# CHANNEL_DELAY.net
KiCad netlist of a schematic drawn in Altium Designer
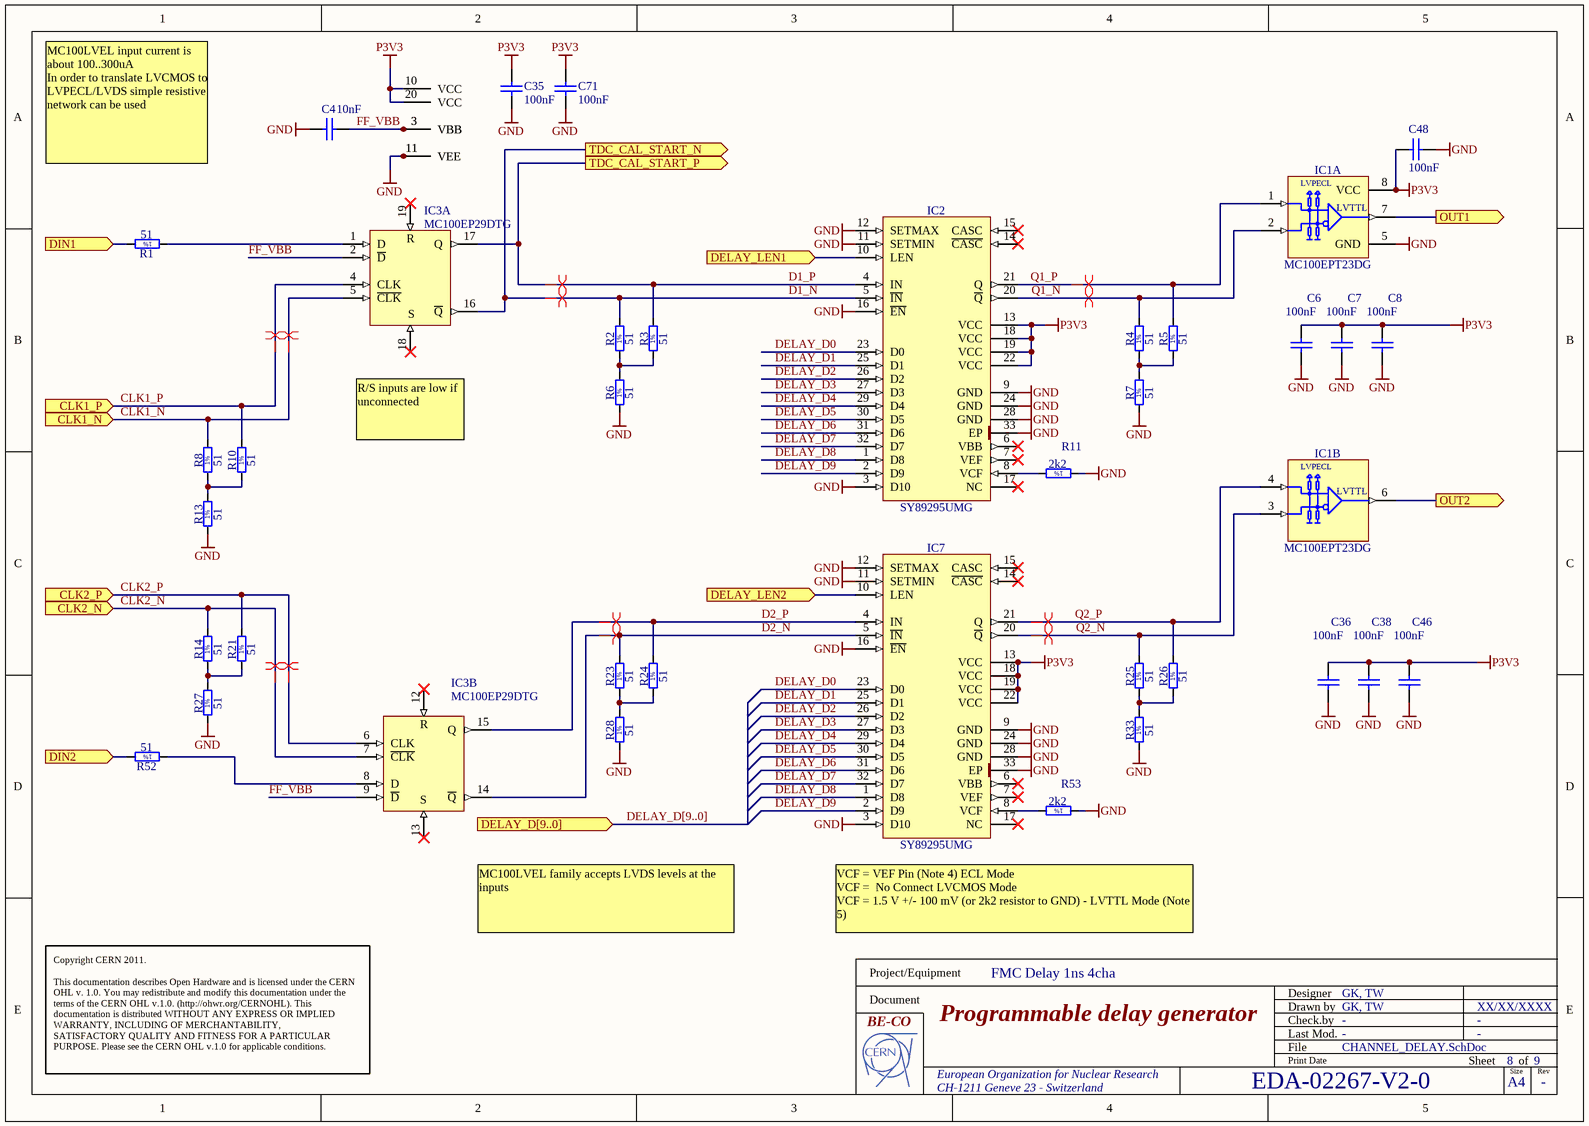
[diagram p0: CHANNEL_DELAY.SchDoc]

(export (version "E")
  (design (tool "Eeschema 10.0.6"))
  (components
    (comp (ref "C4")
      (value "10nF")
      (footprint "CAPC1608X87N")
      (description "Non-polarised capacitor")
      (fields
        (field (name "PART NUMBER") "CC0603_10NF_50V_10%_X7R")
        (field (name "VOLTAGE") "50V")
        (field (name "AUTHOR") "CERN DEM JLC")
      )
      (libsource (lib "Capacitors") (part "Capacitor - non polarized"))
    )
    (comp (ref "C6")
      (value "100nF")
      (footprint "CAPC1608X87N")
      (description "Non-polarised capacitor")
      (fields
        (field (name "MANUFACTURER1 PART NUMBER") "223858615649")
        (field (name "MANUFACTURER") "GENERIC")
        (field (name "AUTHOR") "CERN DEM JLC")
      )
      (libsource (lib "Capacitors") (part "Capacitor - non polarized"))
    )
    (comp (ref "C7")
      (value "100nF")
      (footprint "CAPC1608X87N")
      (description "Non-polarised capacitor")
      (fields
        (field (name "MANUFACTURER1 PART NUMBER") "223858615649")
        (field (name "MANUFACTURER") "GENERIC")
        (field (name "AUTHOR") "CERN DEM JLC")
      )
      (libsource (lib "Capacitors") (part "Capacitor - non polarized"))
    )
    (comp (ref "C8")
      (value "100nF")
      (footprint "CAPC1608X87N")
      (description "Non-polarised capacitor")
      (fields
        (field (name "MANUFACTURER1 PART NUMBER") "223858615649")
        (field (name "MANUFACTURER") "GENERIC")
        (field (name "AUTHOR") "CERN DEM JLC")
      )
      (libsource (lib "Capacitors") (part "Capacitor - non polarized"))
    )
    (comp (ref "C35")
      (value "100nF")
      (footprint "CAPC1608X87N")
      (description "Non-polarised capacitor")
      (fields
        (field (name "MANUFACTURER1 PART NUMBER") "223858615649")
        (field (name "MANUFACTURER") "GENERIC")
        (field (name "AUTHOR") "CERN DEM JLC")
      )
      (libsource (lib "Capacitors") (part "Capacitor - non polarized"))
    )
    (comp (ref "C36")
      (value "100nF")
      (footprint "CAPC1608X87N")
      (description "Non-polarised capacitor")
      (fields
        (field (name "MANUFACTURER1 PART NUMBER") "223858615649")
        (field (name "MANUFACTURER") "GENERIC")
        (field (name "AUTHOR") "CERN DEM JLC")
      )
      (libsource (lib "Capacitors") (part "Capacitor - non polarized"))
    )
    (comp (ref "C38")
      (value "100nF")
      (footprint "CAPC1608X87N")
      (description "Non-polarised capacitor")
      (fields
        (field (name "MANUFACTURER1 PART NUMBER") "223858615649")
        (field (name "MANUFACTURER") "GENERIC")
        (field (name "AUTHOR") "CERN DEM JLC")
      )
      (libsource (lib "Capacitors") (part "Capacitor - non polarized"))
    )
    (comp (ref "C46")
      (value "100nF")
      (footprint "CAPC1608X87N")
      (description "Non-polarised capacitor")
      (fields
        (field (name "MANUFACTURER1 PART NUMBER") "223858615649")
        (field (name "MANUFACTURER") "GENERIC")
        (field (name "AUTHOR") "CERN DEM JLC")
      )
      (libsource (lib "Capacitors") (part "Capacitor - non polarized"))
    )
    (comp (ref "C48")
      (value "100nF")
      (footprint "CAPC1608X87N")
      (description "Non-polarised capacitor")
      (fields
        (field (name "MANUFACTURER1 PART NUMBER") "223858615649")
        (field (name "MANUFACTURER") "GENERIC")
        (field (name "AUTHOR") "CERN DEM JLC")
      )
      (libsource (lib "Capacitors") (part "Capacitor - non polarized"))
    )
    (comp (ref "C71")
      (value "100nF")
      (footprint "CAPC1608X87N")
      (description "Non-polarised capacitor")
      (fields
        (field (name "MANUFACTURER1 PART NUMBER") "223858615649")
        (field (name "MANUFACTURER") "GENERIC")
        (field (name "AUTHOR") "CERN DEM JLC")
      )
      (libsource (lib "Capacitors") (part "Capacitor - non polarized"))
    )
    (comp (ref "IC1")
      (value "MC100EPT23DG")
      (footprint "SOIC127P600X175-8N")
      (description "3.3V Dual Differential LVPECL/LVDS/CML  to LVTTL/LVCMOS Translator")
      (fields (field (name "MANUFACTURER") "ON SEMICONDUCTOR") (field (name "AUTHOR") "CERN DEM JLC"))
      (libsource (lib "ICs And Semiconductors") (part "100EPT23D"))
    )
    (comp (ref "IC2")
      (value "SY89295UMG")
      (footprint "QFN50P500X500X90-33N-S320")
      (description "2.5V/3.3V 1.5GHz Precision LVPECL Programmable Delay")
      (fields (field (name "MANUFACTURER") "MICREL") (field (name "AUTHOR") "CERN DEM JLC"))
      (libsource (lib "ICs And Semiconductors") (part "SY89295UMG"))
    )
    (comp (ref "IC3")
      (value "MC100EP29DTG")
      (footprint "SOP65P640X120-20N")
      (description "3.3V/5V ECL Dual Differential Data and Clock D Flip-Flop With Set and Reset")
      (fields (field (name "MANUFACTURER") "ON SEMICONDUCTOR") (field (name "AUTHOR") "CERN DEM JLC"))
      (libsource (lib "ICs And Semiconductors") (part "100EP29D"))
    )
    (comp (ref "IC7")
      (value "SY89295UMG")
      (footprint "QFN50P500X500X90-33N-S320")
      (description "2.5V/3.3V 1.5GHz Precision LVPECL Programmable Delay")
      (fields (field (name "MANUFACTURER") "MICREL") (field (name "AUTHOR") "CERN DEM JLC"))
      (libsource (lib "ICs And Semiconductors") (part "SY89295UMG"))
    )
    (comp (ref "R1")
      (value "51")
      (footprint "RESC1608X55N")
      (description "Resistor - 1%")
      (fields
        (field (name "PART NUMBER") "R0603_51R_1%_0.1W_100PPM")
        (field (name "POWER") "0.1W")
        (field (name "AUTHOR") "CERN DEM JLC")
      )
      (libsource (lib "Resistors") (part "Resistor - 1%"))
    )
    (comp (ref "R2")
      (value "51")
      (footprint "RESC1608X55N")
      (description "Resistor - 1%")
      (fields
        (field (name "PART NUMBER") "R0603_51R_1%_0.1W_100PPM")
        (field (name "POWER") "0.1W")
        (field (name "AUTHOR") "CERN DEM JLC")
      )
      (libsource (lib "Resistors") (part "Resistor - 1%"))
    )
    (comp (ref "R3")
      (value "51")
      (footprint "RESC1608X55N")
      (description "Resistor - 1%")
      (fields
        (field (name "PART NUMBER") "R0603_51R_1%_0.1W_100PPM")
        (field (name "POWER") "0.1W")
        (field (name "AUTHOR") "CERN DEM JLC")
      )
      (libsource (lib "Resistors") (part "Resistor - 1%"))
    )
    (comp (ref "R4")
      (value "51")
      (footprint "RESC1608X55N")
      (description "Resistor - 1%")
      (fields
        (field (name "PART NUMBER") "R0603_51R_1%_0.1W_100PPM")
        (field (name "POWER") "0.1W")
        (field (name "AUTHOR") "CERN DEM JLC")
      )
      (libsource (lib "Resistors") (part "Resistor - 1%"))
    )
    (comp (ref "R5")
      (value "51")
      (footprint "RESC1608X55N")
      (description "Resistor - 1%")
      (fields
        (field (name "PART NUMBER") "R0603_51R_1%_0.1W_100PPM")
        (field (name "POWER") "0.1W")
        (field (name "AUTHOR") "CERN DEM JLC")
      )
      (libsource (lib "Resistors") (part "Resistor - 1%"))
    )
    (comp (ref "R6")
      (value "51")
      (footprint "RESC1608X55N")
      (description "Resistor - 1%")
      (fields
        (field (name "PART NUMBER") "R0603_51R_1%_0.1W_100PPM")
        (field (name "POWER") "0.1W")
        (field (name "AUTHOR") "CERN DEM JLC")
      )
      (libsource (lib "Resistors") (part "Resistor - 1%"))
    )
    (comp (ref "R7")
      (value "51")
      (footprint "RESC1608X55N")
      (description "Resistor - 1%")
      (fields
        (field (name "PART NUMBER") "R0603_51R_1%_0.1W_100PPM")
        (field (name "POWER") "0.1W")
        (field (name "AUTHOR") "CERN DEM JLC")
      )
      (libsource (lib "Resistors") (part "Resistor - 1%"))
    )
    (comp (ref "R8")
      (value "51")
      (footprint "RESC1608X55N")
      (description "Resistor - 1%")
      (fields
        (field (name "PART NUMBER") "R0603_51R_1%_0.1W_100PPM")
        (field (name "POWER") "0.1W")
        (field (name "AUTHOR") "CERN DEM JLC")
      )
      (libsource (lib "Resistors") (part "Resistor - 1%"))
    )
    (comp (ref "R10")
      (value "51")
      (footprint "RESC1608X55N")
      (description "Resistor - 1%")
      (fields
        (field (name "PART NUMBER") "R0603_51R_1%_0.1W_100PPM")
        (field (name "POWER") "0.1W")
        (field (name "AUTHOR") "CERN DEM JLC")
      )
      (libsource (lib "Resistors") (part "Resistor - 1%"))
    )
    (comp (ref "R11")
      (value "2k2")
      (footprint "RESC1608X55N")
      (description "Resistor - 1%")
      (fields
        (field (name "PART NUMBER") "R0603_2K2_1%_0.1W_100PPM")
        (field (name "POWER") "0.1W")
        (field (name "AUTHOR") "CERN DEM JLC")
      )
      (libsource (lib "Resistors") (part "Resistor - 1%"))
    )
    (comp (ref "R13")
      (value "51")
      (footprint "RESC1608X55N")
      (description "Resistor - 1%")
      (fields
        (field (name "PART NUMBER") "R0603_51R_1%_0.1W_100PPM")
        (field (name "POWER") "0.1W")
        (field (name "AUTHOR") "CERN DEM JLC")
      )
      (libsource (lib "Resistors") (part "Resistor - 1%"))
    )
    (comp (ref "R14")
      (value "51")
      (footprint "RESC1608X55N")
      (description "Resistor - 1%")
      (fields
        (field (name "PART NUMBER") "R0603_51R_1%_0.1W_100PPM")
        (field (name "POWER") "0.1W")
        (field (name "AUTHOR") "CERN DEM JLC")
      )
      (libsource (lib "Resistors") (part "Resistor - 1%"))
    )
    (comp (ref "R21")
      (value "51")
      (footprint "RESC1608X55N")
      (description "Resistor - 1%")
      (fields
        (field (name "PART NUMBER") "R0603_51R_1%_0.1W_100PPM")
        (field (name "POWER") "0.1W")
        (field (name "AUTHOR") "CERN DEM JLC")
      )
      (libsource (lib "Resistors") (part "Resistor - 1%"))
    )
    (comp (ref "R23")
      (value "51")
      (footprint "RESC1608X55N")
      (description "Resistor - 1%")
      (fields
        (field (name "PART NUMBER") "R0603_51R_1%_0.1W_100PPM")
        (field (name "POWER") "0.1W")
        (field (name "AUTHOR") "CERN DEM JLC")
      )
      (libsource (lib "Resistors") (part "Resistor - 1%"))
    )
    (comp (ref "R24")
      (value "51")
      (footprint "RESC1608X55N")
      (description "Resistor - 1%")
      (fields
        (field (name "PART NUMBER") "R0603_51R_1%_0.1W_100PPM")
        (field (name "POWER") "0.1W")
        (field (name "AUTHOR") "CERN DEM JLC")
      )
      (libsource (lib "Resistors") (part "Resistor - 1%"))
    )
    (comp (ref "R25")
      (value "51")
      (footprint "RESC1608X55N")
      (description "Resistor - 1%")
      (fields
        (field (name "PART NUMBER") "R0603_51R_1%_0.1W_100PPM")
        (field (name "POWER") "0.1W")
        (field (name "AUTHOR") "CERN DEM JLC")
      )
      (libsource (lib "Resistors") (part "Resistor - 1%"))
    )
    (comp (ref "R26")
      (value "51")
      (footprint "RESC1608X55N")
      (description "Resistor - 1%")
      (fields
        (field (name "PART NUMBER") "R0603_51R_1%_0.1W_100PPM")
        (field (name "POWER") "0.1W")
        (field (name "AUTHOR") "CERN DEM JLC")
      )
      (libsource (lib "Resistors") (part "Resistor - 1%"))
    )
    (comp (ref "R27")
      (value "51")
      (footprint "RESC1608X55N")
      (description "Resistor - 1%")
      (fields
        (field (name "PART NUMBER") "R0603_51R_1%_0.1W_100PPM")
        (field (name "POWER") "0.1W")
        (field (name "AUTHOR") "CERN DEM JLC")
      )
      (libsource (lib "Resistors") (part "Resistor - 1%"))
    )
    (comp (ref "R28")
      (value "51")
      (footprint "RESC1608X55N")
      (description "Resistor - 1%")
      (fields
        (field (name "PART NUMBER") "R0603_51R_1%_0.1W_100PPM")
        (field (name "POWER") "0.1W")
        (field (name "AUTHOR") "CERN DEM JLC")
      )
      (libsource (lib "Resistors") (part "Resistor - 1%"))
    )
    (comp (ref "R33")
      (value "51")
      (footprint "RESC1608X55N")
      (description "Resistor - 1%")
      (fields
        (field (name "PART NUMBER") "R0603_51R_1%_0.1W_100PPM")
        (field (name "POWER") "0.1W")
        (field (name "AUTHOR") "CERN DEM JLC")
      )
      (libsource (lib "Resistors") (part "Resistor - 1%"))
    )
    (comp (ref "R52")
      (value "51")
      (footprint "RESC1608X55N")
      (description "Resistor - 1%")
      (fields
        (field (name "PART NUMBER") "R0603_51R_1%_0.1W_100PPM")
        (field (name "POWER") "0.1W")
        (field (name "AUTHOR") "CERN DEM JLC")
      )
      (libsource (lib "Resistors") (part "Resistor - 1%"))
    )
    (comp (ref "R53")
      (value "2k2")
      (footprint "RESC1608X55N")
      (description "Resistor - 1%")
      (fields
        (field (name "PART NUMBER") "R0603_2K2_1%_0.1W_100PPM")
        (field (name "POWER") "0.1W")
        (field (name "AUTHOR") "CERN DEM JLC")
      )
      (libsource (lib "Resistors") (part "Resistor - 1%"))
    )
  )
  (nets
    (net (code "1") (name "/CLK1_N") (class "Default")
      (node (ref "IC3") (pin "5") (pinfunction "~{CLK}_5") (pintype "input"))
      (node (ref "R8") (pin "2") (pinfunction "2_2") (pintype "passive"))
    )
    (net (code "2") (name "/CLK1_P") (class "Default")
      (node (ref "IC3") (pin "4") (pinfunction "CLK_4") (pintype "input"))
      (node (ref "R10") (pin "2") (pinfunction "2_2") (pintype "passive"))
    )
    (net (code "3") (name "/CLK2_N") (class "Default")
      (node (ref "IC3") (pin "7") (pinfunction "~{CLK}_7") (pintype "input"))
      (node (ref "R14") (pin "2") (pinfunction "2_2") (pintype "passive"))
    )
    (net (code "4") (name "/CLK2_P") (class "Default")
      (node (ref "IC3") (pin "6") (pinfunction "CLK_6") (pintype "input"))
      (node (ref "R21") (pin "2") (pinfunction "2_2") (pintype "passive"))
    )
    (net (code "5") (name "/D1_N") (class "Default")
      (node (ref "IC2") (pin "5") (pinfunction "~{IN}_5") (pintype "input"))
      (node (ref "IC3") (pin "16") (pinfunction "~{Q}_16") (pintype "output"))
      (node (ref "R2") (pin "2") (pinfunction "2_2") (pintype "passive"))
    )
    (net (code "6") (name "/D1_P") (class "Default")
      (node (ref "IC2") (pin "4") (pinfunction "IN_4") (pintype "input"))
      (node (ref "IC3") (pin "17") (pinfunction "Q_17") (pintype "output"))
      (node (ref "R3") (pin "2") (pinfunction "2_2") (pintype "passive"))
    )
    (net (code "7") (name "/D2_N") (class "Default")
      (node (ref "IC3") (pin "14") (pinfunction "~{Q}_14") (pintype "output"))
      (node (ref "IC7") (pin "5") (pinfunction "~{IN}_5") (pintype "input"))
      (node (ref "R23") (pin "2") (pinfunction "2_2") (pintype "passive"))
    )
    (net (code "8") (name "/D2_P") (class "Default")
      (node (ref "IC3") (pin "15") (pinfunction "Q_15") (pintype "output"))
      (node (ref "IC7") (pin "4") (pinfunction "IN_4") (pintype "input"))
      (node (ref "R24") (pin "2") (pinfunction "2_2") (pintype "passive"))
    )
    (net (code "9") (name "/DELAY_D0") (class "Default")
      (node (ref "IC2") (pin "23") (pinfunction "D0_23") (pintype "input"))
      (node (ref "IC7") (pin "23") (pinfunction "D0_23") (pintype "input"))
    )
    (net (code "10") (name "/DELAY_D1") (class "Default")
      (node (ref "IC2") (pin "25") (pinfunction "D1_25") (pintype "input"))
      (node (ref "IC7") (pin "25") (pinfunction "D1_25") (pintype "input"))
    )
    (net (code "11") (name "/DELAY_D2") (class "Default")
      (node (ref "IC2") (pin "26") (pinfunction "D2_26") (pintype "input"))
      (node (ref "IC7") (pin "26") (pinfunction "D2_26") (pintype "input"))
    )
    (net (code "12") (name "/DELAY_D3") (class "Default")
      (node (ref "IC2") (pin "27") (pinfunction "D3_27") (pintype "input"))
      (node (ref "IC7") (pin "27") (pinfunction "D3_27") (pintype "input"))
    )
    (net (code "13") (name "/DELAY_D4") (class "Default")
      (node (ref "IC2") (pin "29") (pinfunction "D4_29") (pintype "input"))
      (node (ref "IC7") (pin "29") (pinfunction "D4_29") (pintype "input"))
    )
    (net (code "14") (name "/DELAY_D5") (class "Default")
      (node (ref "IC2") (pin "30") (pinfunction "D5_30") (pintype "input"))
      (node (ref "IC7") (pin "30") (pinfunction "D5_30") (pintype "input"))
    )
    (net (code "15") (name "/DELAY_D6") (class "Default")
      (node (ref "IC2") (pin "31") (pinfunction "D6_31") (pintype "input"))
      (node (ref "IC7") (pin "31") (pinfunction "D6_31") (pintype "input"))
    )
    (net (code "16") (name "/DELAY_D7") (class "Default")
      (node (ref "IC2") (pin "32") (pinfunction "D7_32") (pintype "input"))
      (node (ref "IC7") (pin "32") (pinfunction "D7_32") (pintype "input"))
    )
    (net (code "17") (name "/DELAY_D8") (class "Default")
      (node (ref "IC2") (pin "1") (pinfunction "D8_1") (pintype "input"))
      (node (ref "IC7") (pin "1") (pinfunction "D8_1") (pintype "input"))
    )
    (net (code "18") (name "/DELAY_D9") (class "Default")
      (node (ref "IC2") (pin "2") (pinfunction "D9_2") (pintype "input"))
      (node (ref "IC7") (pin "2") (pinfunction "D9_2") (pintype "input"))
    )
    (net (code "20") (name "/DELAY_LEN1") (class "Default")
      (node (ref "IC2") (pin "10") (pinfunction "LEN_10") (pintype "input"))
    )
    (net (code "21") (name "/DELAY_LEN2") (class "Default")
      (node (ref "IC7") (pin "10") (pinfunction "LEN_10") (pintype "input"))
    )
    (net (code "22") (name "/DIN1") (class "Default")
      (node (ref "R1") (pin "2") (pinfunction "2_2") (pintype "passive"))
    )
    (net (code "23") (name "/DIN2") (class "Default")
      (node (ref "R52") (pin "2") (pinfunction "2_2") (pintype "passive"))
    )
    (net (code "24") (name "/FF_VBB") (class "Default")
      (node (ref "C4") (pin "1") (pinfunction "1_1") (pintype "passive"))
      (node (ref "IC3") (pin "2") (pinfunction "~{D}_2") (pintype "input"))
      (node (ref "IC3") (pin "3") (pinfunction "VBB_3") (pintype "power_in"))
      (node (ref "IC3") (pin "9") (pinfunction "~{D}_9") (pintype "input"))
    )
    (net (code "25") (name "/OUT1") (class "Default")
      (node (ref "IC1") (pin "7") (pinfunction "Q0_7") (pintype "output"))
    )
    (net (code "26") (name "/OUT2") (class "Default")
      (node (ref "IC1") (pin "6") (pinfunction "Q0_6") (pintype "output"))
    )
    (net (code "27") (name "/Q1_N") (class "Default")
      (node (ref "IC1") (pin "2") (pinfunction "~{D0}_2") (pintype "input"))
      (node (ref "IC2") (pin "20") (pinfunction "~{Q}_20") (pintype "output"))
      (node (ref "R4") (pin "2") (pinfunction "2_2") (pintype "passive"))
    )
    (net (code "28") (name "/Q1_P") (class "Default")
      (node (ref "IC1") (pin "1") (pinfunction "D0_1") (pintype "input"))
      (node (ref "IC2") (pin "21") (pinfunction "Q_21") (pintype "output"))
      (node (ref "R5") (pin "2") (pinfunction "2_2") (pintype "passive"))
    )
    (net (code "29") (name "/Q2_N") (class "Default")
      (node (ref "IC1") (pin "3") (pinfunction "~{D0}_3") (pintype "input"))
      (node (ref "IC7") (pin "20") (pinfunction "~{Q}_20") (pintype "output"))
      (node (ref "R25") (pin "2") (pinfunction "2_2") (pintype "passive"))
    )
    (net (code "30") (name "/Q2_P") (class "Default")
      (node (ref "IC1") (pin "4") (pinfunction "D0_4") (pintype "input"))
      (node (ref "IC7") (pin "21") (pinfunction "Q_21") (pintype "output"))
      (node (ref "R26") (pin "2") (pinfunction "2_2") (pintype "passive"))
    )
    (net (code "31") (name "GND") (class "Default")
      (node (ref "C35") (pin "1") (pinfunction "1_1") (pintype "passive"))
      (node (ref "C36") (pin "2") (pinfunction "2_2") (pintype "passive"))
      (node (ref "C38") (pin "2") (pinfunction "2_2") (pintype "passive"))
      (node (ref "C4") (pin "2") (pinfunction "2_2") (pintype "passive"))
      (node (ref "C46") (pin "2") (pinfunction "2_2") (pintype "passive"))
      (node (ref "C48") (pin "2") (pinfunction "2_2") (pintype "passive"))
      (node (ref "C6") (pin "2") (pinfunction "2_2") (pintype "passive"))
      (node (ref "C7") (pin "2") (pinfunction "2_2") (pintype "passive"))
      (node (ref "C71") (pin "1") (pinfunction "1_1") (pintype "passive"))
      (node (ref "C8") (pin "2") (pinfunction "2_2") (pintype "passive"))
      (node (ref "IC1") (pin "5") (pinfunction "GND_5") (pintype "power_in"))
      (node (ref "IC2") (pin "11") (pinfunction "SETMIN_11") (pintype "input"))
      (node (ref "IC2") (pin "12") (pinfunction "SETMAX_12") (pintype "input"))
      (node (ref "IC2") (pin "16") (pinfunction "~{EN}_16") (pintype "input"))
      (node (ref "IC2") (pin "24") (pinfunction "GND_24") (pintype "power_in"))
      (node (ref "IC2") (pin "28") (pinfunction "GND_28") (pintype "power_in"))
      (node (ref "IC2") (pin "3") (pinfunction "D10_3") (pintype "input"))
      (node (ref "IC2") (pin "33") (pinfunction "EP_33") (pintype "power_in"))
      (node (ref "IC2") (pin "9") (pinfunction "GND_9") (pintype "power_in"))
      (node (ref "IC3") (pin "11") (pinfunction "VEE_11") (pintype "power_in"))
      (node (ref "IC7") (pin "11") (pinfunction "SETMIN_11") (pintype "input"))
      (node (ref "IC7") (pin "12") (pinfunction "SETMAX_12") (pintype "input"))
      (node (ref "IC7") (pin "16") (pinfunction "~{EN}_16") (pintype "input"))
      (node (ref "IC7") (pin "24") (pinfunction "GND_24") (pintype "power_in"))
      (node (ref "IC7") (pin "28") (pinfunction "GND_28") (pintype "power_in"))
      (node (ref "IC7") (pin "3") (pinfunction "D10_3") (pintype "input"))
      (node (ref "IC7") (pin "33") (pinfunction "EP_33") (pintype "power_in"))
      (node (ref "IC7") (pin "9") (pinfunction "GND_9") (pintype "power_in"))
      (node (ref "R11") (pin "1") (pinfunction "1_1") (pintype "passive"))
      (node (ref "R13") (pin "1") (pinfunction "1_1") (pintype "passive"))
      (node (ref "R27") (pin "1") (pinfunction "1_1") (pintype "passive"))
      (node (ref "R28") (pin "1") (pinfunction "1_1") (pintype "passive"))
      (node (ref "R33") (pin "1") (pinfunction "1_1") (pintype "passive"))
      (node (ref "R53") (pin "1") (pinfunction "1_1") (pintype "passive"))
      (node (ref "R6") (pin "1") (pinfunction "1_1") (pintype "passive"))
      (node (ref "R7") (pin "1") (pinfunction "1_1") (pintype "passive"))
    )
    (net (code "32") (name "Net-(IC2-VCF)") (class "Default")
      (node (ref "IC2") (pin "8") (pinfunction "VCF_8") (pintype "input"))
      (node (ref "R11") (pin "2") (pinfunction "2_2") (pintype "passive"))
    )
    (net (code "33") (name "Net-(IC3A-D)") (class "Default")
      (node (ref "IC3") (pin "1") (pinfunction "D_1") (pintype "input"))
      (node (ref "R1") (pin "1") (pinfunction "1_1") (pintype "passive"))
    )
    (net (code "34") (name "Net-(IC3B-D)") (class "Default")
      (node (ref "IC3") (pin "8") (pinfunction "D_8") (pintype "input"))
      (node (ref "R52") (pin "1") (pinfunction "1_1") (pintype "passive"))
    )
    (net (code "35") (name "Net-(IC7-VCF)") (class "Default")
      (node (ref "IC7") (pin "8") (pinfunction "VCF_8") (pintype "input"))
      (node (ref "R53") (pin "2") (pinfunction "2_2") (pintype "passive"))
    )
    (net (code "36") (name "Net-(R2-Pad1)") (class "Default")
      (node (ref "R2") (pin "1") (pinfunction "1_1") (pintype "passive"))
      (node (ref "R3") (pin "1") (pinfunction "1_1") (pintype "passive"))
      (node (ref "R6") (pin "2") (pinfunction "2_2") (pintype "passive"))
    )
    (net (code "37") (name "Net-(R4-Pad1)") (class "Default")
      (node (ref "R4") (pin "1") (pinfunction "1_1") (pintype "passive"))
      (node (ref "R5") (pin "1") (pinfunction "1_1") (pintype "passive"))
      (node (ref "R7") (pin "2") (pinfunction "2_2") (pintype "passive"))
    )
    (net (code "38") (name "Net-(R10-Pad1)") (class "Default")
      (node (ref "R10") (pin "1") (pinfunction "1_1") (pintype "passive"))
      (node (ref "R13") (pin "2") (pinfunction "2_2") (pintype "passive"))
      (node (ref "R8") (pin "1") (pinfunction "1_1") (pintype "passive"))
    )
    (net (code "39") (name "Net-(R14-Pad1)") (class "Default")
      (node (ref "R14") (pin "1") (pinfunction "1_1") (pintype "passive"))
      (node (ref "R21") (pin "1") (pinfunction "1_1") (pintype "passive"))
      (node (ref "R27") (pin "2") (pinfunction "2_2") (pintype "passive"))
    )
    (net (code "40") (name "Net-(R23-Pad1)") (class "Default")
      (node (ref "R23") (pin "1") (pinfunction "1_1") (pintype "passive"))
      (node (ref "R24") (pin "1") (pinfunction "1_1") (pintype "passive"))
      (node (ref "R28") (pin "2") (pinfunction "2_2") (pintype "passive"))
    )
    (net (code "41") (name "Net-(R25-Pad1)") (class "Default")
      (node (ref "R25") (pin "1") (pinfunction "1_1") (pintype "passive"))
      (node (ref "R26") (pin "1") (pinfunction "1_1") (pintype "passive"))
      (node (ref "R33") (pin "2") (pinfunction "2_2") (pintype "passive"))
    )
    (net (code "42") (name "P3V3") (class "Default")
      (node (ref "C35") (pin "2") (pinfunction "2_2") (pintype "passive"))
      (node (ref "C36") (pin "1") (pinfunction "1_1") (pintype "passive"))
      (node (ref "C38") (pin "1") (pinfunction "1_1") (pintype "passive"))
      (node (ref "C46") (pin "1") (pinfunction "1_1") (pintype "passive"))
      (node (ref "C48") (pin "1") (pinfunction "1_1") (pintype "passive"))
      (node (ref "C6") (pin "1") (pinfunction "1_1") (pintype "passive"))
      (node (ref "C7") (pin "1") (pinfunction "1_1") (pintype "passive"))
      (node (ref "C71") (pin "2") (pinfunction "2_2") (pintype "passive"))
      (node (ref "C8") (pin "1") (pinfunction "1_1") (pintype "passive"))
      (node (ref "IC1") (pin "8") (pinfunction "VCC_8") (pintype "power_in"))
      (node (ref "IC2") (pin "13") (pinfunction "VCC_13") (pintype "power_in"))
      (node (ref "IC2") (pin "18") (pinfunction "VCC_18") (pintype "power_in"))
      (node (ref "IC2") (pin "19") (pinfunction "VCC_19") (pintype "power_in"))
      (node (ref "IC2") (pin "22") (pinfunction "VCC_22") (pintype "power_in"))
      (node (ref "IC3") (pin "10") (pinfunction "VCC_10") (pintype "power_in"))
      (node (ref "IC3") (pin "20") (pinfunction "VCC_20") (pintype "power_in"))
      (node (ref "IC7") (pin "13") (pinfunction "VCC_13") (pintype "power_in"))
      (node (ref "IC7") (pin "18") (pinfunction "VCC_18") (pintype "power_in"))
      (node (ref "IC7") (pin "19") (pinfunction "VCC_19") (pintype "power_in"))
      (node (ref "IC7") (pin "22") (pinfunction "VCC_22") (pintype "power_in"))
    )
    (net (code "43") (name "unconnected-(IC2-CASC-Pad15)") (class "Default")
      (node (ref "IC2") (pin "15") (pinfunction "CASC_15") (pintype "input+no_connect"))
    )
    (net (code "44") (name "unconnected-(IC2-NC-Pad17)") (class "Default")
      (node (ref "IC2") (pin "17") (pinfunction "NC_17") (pintype "passive+no_connect"))
    )
    (net (code "45") (name "unconnected-(IC2-VBB-Pad6)") (class "Default")
      (node (ref "IC2") (pin "6") (pinfunction "VBB_6") (pintype "output+no_connect"))
    )
    (net (code "46") (name "unconnected-(IC2-VEF-Pad7)") (class "Default")
      (node (ref "IC2") (pin "7") (pinfunction "VEF_7") (pintype "output+no_connect"))
    )
    (net (code "47") (name "unconnected-(IC2-~{CASC}-Pad14)") (class "Default")
      (node (ref "IC2") (pin "14") (pinfunction "~{CASC}_14") (pintype "input+no_connect"))
    )
    (net (code "48") (name "unconnected-(IC3A-R-Pad19)") (class "Default")
      (node (ref "IC3") (pin "19") (pinfunction "R_19") (pintype "input+no_connect"))
    )
    (net (code "49") (name "unconnected-(IC3A-S-Pad18)") (class "Default")
      (node (ref "IC3") (pin "18") (pinfunction "S_18") (pintype "input+no_connect"))
    )
    (net (code "50") (name "unconnected-(IC3B-R-Pad12)") (class "Default")
      (node (ref "IC3") (pin "12") (pinfunction "R_12") (pintype "input+no_connect"))
    )
    (net (code "51") (name "unconnected-(IC3B-S-Pad13)") (class "Default")
      (node (ref "IC3") (pin "13") (pinfunction "S_13") (pintype "input+no_connect"))
    )
    (net (code "52") (name "unconnected-(IC7-CASC-Pad15)") (class "Default")
      (node (ref "IC7") (pin "15") (pinfunction "CASC_15") (pintype "input+no_connect"))
    )
    (net (code "53") (name "unconnected-(IC7-NC-Pad17)") (class "Default")
      (node (ref "IC7") (pin "17") (pinfunction "NC_17") (pintype "passive+no_connect"))
    )
    (net (code "54") (name "unconnected-(IC7-VBB-Pad6)") (class "Default")
      (node (ref "IC7") (pin "6") (pinfunction "VBB_6") (pintype "output+no_connect"))
    )
    (net (code "55") (name "unconnected-(IC7-VEF-Pad7)") (class "Default")
      (node (ref "IC7") (pin "7") (pinfunction "VEF_7") (pintype "output+no_connect"))
    )
    (net (code "56") (name "unconnected-(IC7-~{CASC}-Pad14)") (class "Default")
      (node (ref "IC7") (pin "14") (pinfunction "~{CASC}_14") (pintype "input+no_connect"))
    )
  )
)
